# d150_in14.net
KiCad netlist of a schematic drawn in EAGLE
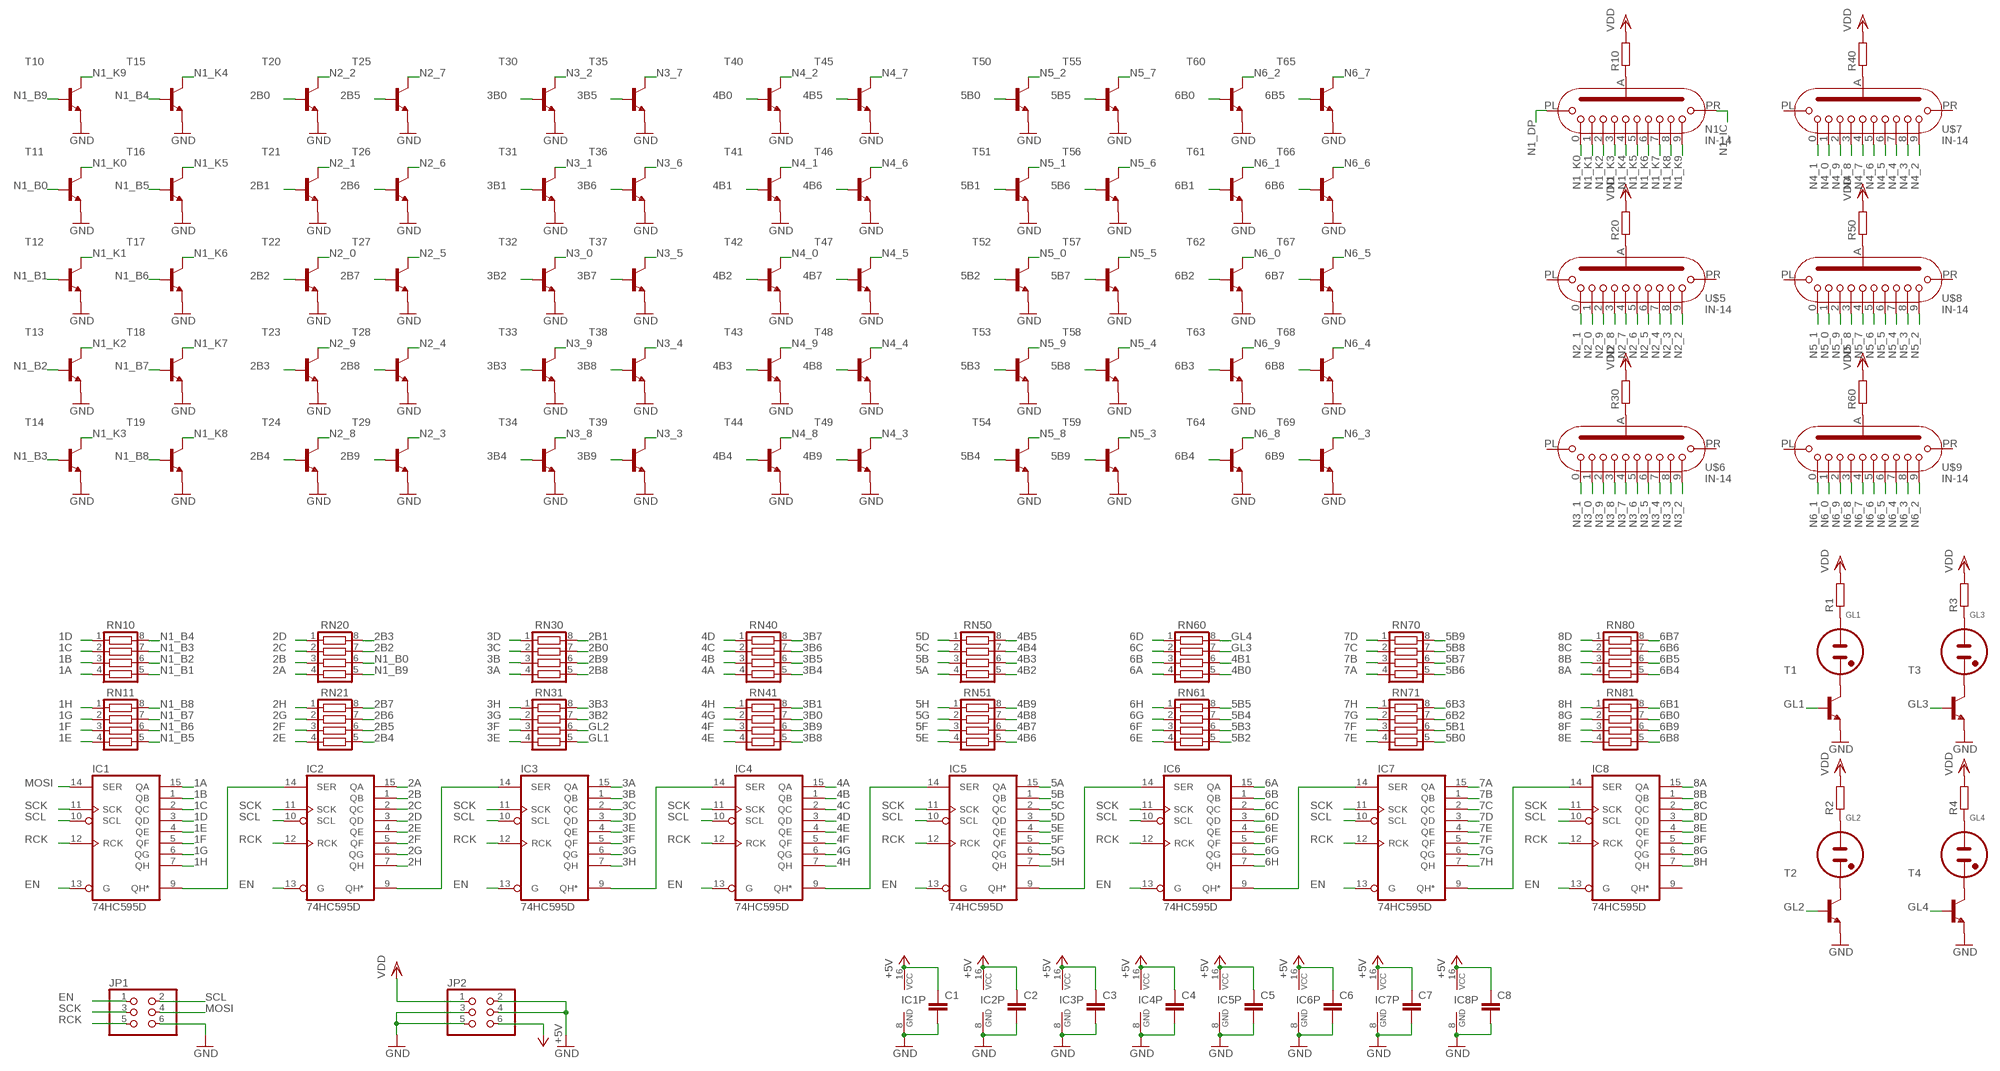
[diagram p0: schematic, sheet 1]

(export (version "E")
  (design (tool "Eeschema 10.0.6"))
  (components
    (comp (ref "C1")
      (value "C-EUC0603")
      (footprint "eagle-import:C0603")
      (libsource (lib "eagle-import") (part "C-EUC0603"))
    )
    (comp (ref "C2")
      (value "C-EUC0603")
      (footprint "eagle-import:C0603")
      (libsource (lib "eagle-import") (part "C-EUC0603"))
    )
    (comp (ref "C3")
      (value "C-EUC0603")
      (footprint "eagle-import:C0603")
      (libsource (lib "eagle-import") (part "C-EUC0603"))
    )
    (comp (ref "C4")
      (value "C-EUC0603")
      (footprint "eagle-import:C0603")
      (libsource (lib "eagle-import") (part "C-EUC0603"))
    )
    (comp (ref "C5")
      (value "C-EUC0603")
      (footprint "eagle-import:C0603")
      (libsource (lib "eagle-import") (part "C-EUC0603"))
    )
    (comp (ref "C6")
      (value "C-EUC0603")
      (footprint "eagle-import:C0603")
      (libsource (lib "eagle-import") (part "C-EUC0603"))
    )
    (comp (ref "C7")
      (value "C-EUC0603")
      (footprint "eagle-import:C0603")
      (libsource (lib "eagle-import") (part "C-EUC0603"))
    )
    (comp (ref "C8")
      (value "C-EUC0603")
      (footprint "eagle-import:C0603")
      (libsource (lib "eagle-import") (part "C-EUC0603"))
    )
    (comp (ref "GL1")
      (value "NE2-NEON-BULB-DRILL")
      (footprint "eagle-import:NE2-NEON-BULB-DRILL")
      (libsource (lib "eagle-import") (part "NE2-NEON-BULB-DRILL"))
    )
    (comp (ref "GL2")
      (value "NE2-NEON-BULB-DRILL")
      (footprint "eagle-import:NE2-NEON-BULB-DRILL")
      (libsource (lib "eagle-import") (part "NE2-NEON-BULB-DRILL"))
    )
    (comp (ref "GL3")
      (value "NE2-NEON-BULB-DRILL")
      (footprint "eagle-import:NE2-NEON-BULB-DRILL")
      (libsource (lib "eagle-import") (part "NE2-NEON-BULB-DRILL"))
    )
    (comp (ref "GL4")
      (value "NE2-NEON-BULB-DRILL")
      (footprint "eagle-import:NE2-NEON-BULB-DRILL")
      (libsource (lib "eagle-import") (part "NE2-NEON-BULB-DRILL"))
    )
    (comp (ref "IC1")
      (value "74HC595D")
      (footprint "eagle-import:SO16")
      (libsource (lib "eagle-import") (part "74595DHC"))
    )
    (comp (ref "IC2")
      (value "74HC595D")
      (footprint "eagle-import:SO16")
      (libsource (lib "eagle-import") (part "74595DHC"))
    )
    (comp (ref "IC3")
      (value "74HC595D")
      (footprint "eagle-import:SO16")
      (libsource (lib "eagle-import") (part "74595DHC"))
    )
    (comp (ref "IC4")
      (value "74HC595D")
      (footprint "eagle-import:SO16")
      (libsource (lib "eagle-import") (part "74595DHC"))
    )
    (comp (ref "IC5")
      (value "74HC595D")
      (footprint "eagle-import:SO16")
      (libsource (lib "eagle-import") (part "74595DHC"))
    )
    (comp (ref "IC6")
      (value "74HC595D")
      (footprint "eagle-import:SO16")
      (libsource (lib "eagle-import") (part "74595DHC"))
    )
    (comp (ref "IC7")
      (value "74HC595D")
      (footprint "eagle-import:SO16")
      (libsource (lib "eagle-import") (part "74595DHC"))
    )
    (comp (ref "IC8")
      (value "74HC595D")
      (footprint "eagle-import:SO16")
      (libsource (lib "eagle-import") (part "74595DHC"))
    )
    (comp (ref "JP1")
      (value "PINHD-2X3_2.54-SMD")
      (footprint "eagle-import:2X03SMD")
      (libsource (lib "eagle-import") (part "PINHD-2X3_2.54-SMD"))
    )
    (comp (ref "JP2")
      (value "PINHD-2X3_2.54-SMD")
      (footprint "eagle-import:2X03SMD")
      (libsource (lib "eagle-import") (part "PINHD-2X3_2.54-SMD"))
    )
    (comp (ref "N1")
      (value "IN-14")
      (footprint "eagle-import:IN-14")
      (libsource (lib "eagle-import") (part "IN-14"))
    )
    (comp (ref "R1")
      (value "R-EU_R0603")
      (footprint "eagle-import:R0603")
      (libsource (lib "eagle-import") (part "R-EU_R0603"))
    )
    (comp (ref "R2")
      (value "R-EU_R0603")
      (footprint "eagle-import:R0603")
      (libsource (lib "eagle-import") (part "R-EU_R0603"))
    )
    (comp (ref "R3")
      (value "R-EU_R0603")
      (footprint "eagle-import:R0603")
      (libsource (lib "eagle-import") (part "R-EU_R0603"))
    )
    (comp (ref "R4")
      (value "R-EU_R0603")
      (footprint "eagle-import:R0603")
      (libsource (lib "eagle-import") (part "R-EU_R0603"))
    )
    (comp (ref "R10")
      (value "R-EU_R0603")
      (footprint "eagle-import:R0603")
      (libsource (lib "eagle-import") (part "R-EU_R0603"))
    )
    (comp (ref "R20")
      (value "R-EU_R0603")
      (footprint "eagle-import:R0603")
      (libsource (lib "eagle-import") (part "R-EU_R0603"))
    )
    (comp (ref "R30")
      (value "R-EU_R0603")
      (footprint "eagle-import:R0603")
      (libsource (lib "eagle-import") (part "R-EU_R0603"))
    )
    (comp (ref "R40")
      (value "R-EU_R0603")
      (footprint "eagle-import:R0603")
      (libsource (lib "eagle-import") (part "R-EU_R0603"))
    )
    (comp (ref "R50")
      (value "R-EU_R0603")
      (footprint "eagle-import:R0603")
      (libsource (lib "eagle-import") (part "R-EU_R0603"))
    )
    (comp (ref "R60")
      (value "R-EU_R0603")
      (footprint "eagle-import:R0603")
      (libsource (lib "eagle-import") (part "R-EU_R0603"))
    )
    (comp (ref "RN10")
      (value "CTS742C083")
      (footprint "eagle-import:CTS742C083")
      (fields (field (name "OC_FARNELL") "unknown") (field (name "OC_NEWARK") "unknown"))
      (libsource (lib "eagle-import") (part "CTS742C083"))
    )
    (comp (ref "RN11")
      (value "CTS742C083")
      (footprint "eagle-import:CTS742C083")
      (fields (field (name "OC_FARNELL") "unknown") (field (name "OC_NEWARK") "unknown"))
      (libsource (lib "eagle-import") (part "CTS742C083"))
    )
    (comp (ref "RN20")
      (value "CTS742C083")
      (footprint "eagle-import:CTS742C083")
      (fields (field (name "OC_FARNELL") "unknown") (field (name "OC_NEWARK") "unknown"))
      (libsource (lib "eagle-import") (part "CTS742C083"))
    )
    (comp (ref "RN21")
      (value "CTS742C083")
      (footprint "eagle-import:CTS742C083")
      (fields (field (name "OC_FARNELL") "unknown") (field (name "OC_NEWARK") "unknown"))
      (libsource (lib "eagle-import") (part "CTS742C083"))
    )
    (comp (ref "RN30")
      (value "CTS742C083")
      (footprint "eagle-import:CTS742C083")
      (fields (field (name "OC_FARNELL") "unknown") (field (name "OC_NEWARK") "unknown"))
      (libsource (lib "eagle-import") (part "CTS742C083"))
    )
    (comp (ref "RN31")
      (value "CTS742C083")
      (footprint "eagle-import:CTS742C083")
      (fields (field (name "OC_FARNELL") "unknown") (field (name "OC_NEWARK") "unknown"))
      (libsource (lib "eagle-import") (part "CTS742C083"))
    )
    (comp (ref "RN40")
      (value "CTS742C083")
      (footprint "eagle-import:CTS742C083")
      (fields (field (name "OC_FARNELL") "unknown") (field (name "OC_NEWARK") "unknown"))
      (libsource (lib "eagle-import") (part "CTS742C083"))
    )
    (comp (ref "RN41")
      (value "CTS742C083")
      (footprint "eagle-import:CTS742C083")
      (fields (field (name "OC_FARNELL") "unknown") (field (name "OC_NEWARK") "unknown"))
      (libsource (lib "eagle-import") (part "CTS742C083"))
    )
    (comp (ref "RN50")
      (value "CTS742C083")
      (footprint "eagle-import:CTS742C083")
      (fields (field (name "OC_FARNELL") "unknown") (field (name "OC_NEWARK") "unknown"))
      (libsource (lib "eagle-import") (part "CTS742C083"))
    )
    (comp (ref "RN51")
      (value "CTS742C083")
      (footprint "eagle-import:CTS742C083")
      (fields (field (name "OC_FARNELL") "unknown") (field (name "OC_NEWARK") "unknown"))
      (libsource (lib "eagle-import") (part "CTS742C083"))
    )
    (comp (ref "RN60")
      (value "CTS742C083")
      (footprint "eagle-import:CTS742C083")
      (fields (field (name "OC_FARNELL") "unknown") (field (name "OC_NEWARK") "unknown"))
      (libsource (lib "eagle-import") (part "CTS742C083"))
    )
    (comp (ref "RN61")
      (value "CTS742C083")
      (footprint "eagle-import:CTS742C083")
      (fields (field (name "OC_FARNELL") "unknown") (field (name "OC_NEWARK") "unknown"))
      (libsource (lib "eagle-import") (part "CTS742C083"))
    )
    (comp (ref "RN70")
      (value "CTS742C083")
      (footprint "eagle-import:CTS742C083")
      (fields (field (name "OC_FARNELL") "unknown") (field (name "OC_NEWARK") "unknown"))
      (libsource (lib "eagle-import") (part "CTS742C083"))
    )
    (comp (ref "RN71")
      (value "CTS742C083")
      (footprint "eagle-import:CTS742C083")
      (fields (field (name "OC_FARNELL") "unknown") (field (name "OC_NEWARK") "unknown"))
      (libsource (lib "eagle-import") (part "CTS742C083"))
    )
    (comp (ref "RN80")
      (value "CTS742C083")
      (footprint "eagle-import:CTS742C083")
      (fields (field (name "OC_FARNELL") "unknown") (field (name "OC_NEWARK") "unknown"))
      (libsource (lib "eagle-import") (part "CTS742C083"))
    )
    (comp (ref "RN81")
      (value "CTS742C083")
      (footprint "eagle-import:CTS742C083")
      (fields (field (name "OC_FARNELL") "unknown") (field (name "OC_NEWARK") "unknown"))
      (libsource (lib "eagle-import") (part "CTS742C083"))
    )
    (comp (ref "T1")
      (value "SMBTA42")
      (footprint "eagle-import:SOT23")
      (libsource (lib "eagle-import") (part "SMBTA42"))
    )
    (comp (ref "T2")
      (value "SMBTA42")
      (footprint "eagle-import:SOT23")
      (libsource (lib "eagle-import") (part "SMBTA42"))
    )
    (comp (ref "T3")
      (value "SMBTA42")
      (footprint "eagle-import:SOT23")
      (libsource (lib "eagle-import") (part "SMBTA42"))
    )
    (comp (ref "T4")
      (value "SMBTA42")
      (footprint "eagle-import:SOT23")
      (libsource (lib "eagle-import") (part "SMBTA42"))
    )
    (comp (ref "T10")
      (value "SMBTA42")
      (footprint "eagle-import:SOT23")
      (libsource (lib "eagle-import") (part "SMBTA42"))
    )
    (comp (ref "T11")
      (value "SMBTA42")
      (footprint "eagle-import:SOT23")
      (libsource (lib "eagle-import") (part "SMBTA42"))
    )
    (comp (ref "T12")
      (value "SMBTA42")
      (footprint "eagle-import:SOT23")
      (libsource (lib "eagle-import") (part "SMBTA42"))
    )
    (comp (ref "T13")
      (value "SMBTA42")
      (footprint "eagle-import:SOT23")
      (libsource (lib "eagle-import") (part "SMBTA42"))
    )
    (comp (ref "T14")
      (value "SMBTA42")
      (footprint "eagle-import:SOT23")
      (libsource (lib "eagle-import") (part "SMBTA42"))
    )
    (comp (ref "T15")
      (value "SMBTA42")
      (footprint "eagle-import:SOT23")
      (libsource (lib "eagle-import") (part "SMBTA42"))
    )
    (comp (ref "T16")
      (value "SMBTA42")
      (footprint "eagle-import:SOT23")
      (libsource (lib "eagle-import") (part "SMBTA42"))
    )
    (comp (ref "T17")
      (value "SMBTA42")
      (footprint "eagle-import:SOT23")
      (libsource (lib "eagle-import") (part "SMBTA42"))
    )
    (comp (ref "T18")
      (value "SMBTA42")
      (footprint "eagle-import:SOT23")
      (libsource (lib "eagle-import") (part "SMBTA42"))
    )
    (comp (ref "T19")
      (value "SMBTA42")
      (footprint "eagle-import:SOT23")
      (libsource (lib "eagle-import") (part "SMBTA42"))
    )
    (comp (ref "T20")
      (value "SMBTA42")
      (footprint "eagle-import:SOT23")
      (libsource (lib "eagle-import") (part "SMBTA42"))
    )
    (comp (ref "T21")
      (value "SMBTA42")
      (footprint "eagle-import:SOT23")
      (libsource (lib "eagle-import") (part "SMBTA42"))
    )
    (comp (ref "T22")
      (value "SMBTA42")
      (footprint "eagle-import:SOT23")
      (libsource (lib "eagle-import") (part "SMBTA42"))
    )
    (comp (ref "T23")
      (value "SMBTA42")
      (footprint "eagle-import:SOT23")
      (libsource (lib "eagle-import") (part "SMBTA42"))
    )
    (comp (ref "T24")
      (value "SMBTA42")
      (footprint "eagle-import:SOT23")
      (libsource (lib "eagle-import") (part "SMBTA42"))
    )
    (comp (ref "T25")
      (value "SMBTA42")
      (footprint "eagle-import:SOT23")
      (libsource (lib "eagle-import") (part "SMBTA42"))
    )
    (comp (ref "T26")
      (value "SMBTA42")
      (footprint "eagle-import:SOT23")
      (libsource (lib "eagle-import") (part "SMBTA42"))
    )
    (comp (ref "T27")
      (value "SMBTA42")
      (footprint "eagle-import:SOT23")
      (libsource (lib "eagle-import") (part "SMBTA42"))
    )
    (comp (ref "T28")
      (value "SMBTA42")
      (footprint "eagle-import:SOT23")
      (libsource (lib "eagle-import") (part "SMBTA42"))
    )
    (comp (ref "T29")
      (value "SMBTA42")
      (footprint "eagle-import:SOT23")
      (libsource (lib "eagle-import") (part "SMBTA42"))
    )
    (comp (ref "T30")
      (value "SMBTA42")
      (footprint "eagle-import:SOT23")
      (libsource (lib "eagle-import") (part "SMBTA42"))
    )
    (comp (ref "T31")
      (value "SMBTA42")
      (footprint "eagle-import:SOT23")
      (libsource (lib "eagle-import") (part "SMBTA42"))
    )
    (comp (ref "T32")
      (value "SMBTA42")
      (footprint "eagle-import:SOT23")
      (libsource (lib "eagle-import") (part "SMBTA42"))
    )
    (comp (ref "T33")
      (value "SMBTA42")
      (footprint "eagle-import:SOT23")
      (libsource (lib "eagle-import") (part "SMBTA42"))
    )
    (comp (ref "T34")
      (value "SMBTA42")
      (footprint "eagle-import:SOT23")
      (libsource (lib "eagle-import") (part "SMBTA42"))
    )
    (comp (ref "T35")
      (value "SMBTA42")
      (footprint "eagle-import:SOT23")
      (libsource (lib "eagle-import") (part "SMBTA42"))
    )
    (comp (ref "T36")
      (value "SMBTA42")
      (footprint "eagle-import:SOT23")
      (libsource (lib "eagle-import") (part "SMBTA42"))
    )
    (comp (ref "T37")
      (value "SMBTA42")
      (footprint "eagle-import:SOT23")
      (libsource (lib "eagle-import") (part "SMBTA42"))
    )
    (comp (ref "T38")
      (value "SMBTA42")
      (footprint "eagle-import:SOT23")
      (libsource (lib "eagle-import") (part "SMBTA42"))
    )
    (comp (ref "T39")
      (value "SMBTA42")
      (footprint "eagle-import:SOT23")
      (libsource (lib "eagle-import") (part "SMBTA42"))
    )
    (comp (ref "T40")
      (value "SMBTA42")
      (footprint "eagle-import:SOT23")
      (libsource (lib "eagle-import") (part "SMBTA42"))
    )
    (comp (ref "T41")
      (value "SMBTA42")
      (footprint "eagle-import:SOT23")
      (libsource (lib "eagle-import") (part "SMBTA42"))
    )
    (comp (ref "T42")
      (value "SMBTA42")
      (footprint "eagle-import:SOT23")
      (libsource (lib "eagle-import") (part "SMBTA42"))
    )
    (comp (ref "T43")
      (value "SMBTA42")
      (footprint "eagle-import:SOT23")
      (libsource (lib "eagle-import") (part "SMBTA42"))
    )
    (comp (ref "T44")
      (value "SMBTA42")
      (footprint "eagle-import:SOT23")
      (libsource (lib "eagle-import") (part "SMBTA42"))
    )
    (comp (ref "T45")
      (value "SMBTA42")
      (footprint "eagle-import:SOT23")
      (libsource (lib "eagle-import") (part "SMBTA42"))
    )
    (comp (ref "T46")
      (value "SMBTA42")
      (footprint "eagle-import:SOT23")
      (libsource (lib "eagle-import") (part "SMBTA42"))
    )
    (comp (ref "T47")
      (value "SMBTA42")
      (footprint "eagle-import:SOT23")
      (libsource (lib "eagle-import") (part "SMBTA42"))
    )
    (comp (ref "T48")
      (value "SMBTA42")
      (footprint "eagle-import:SOT23")
      (libsource (lib "eagle-import") (part "SMBTA42"))
    )
    (comp (ref "T49")
      (value "SMBTA42")
      (footprint "eagle-import:SOT23")
      (libsource (lib "eagle-import") (part "SMBTA42"))
    )
    (comp (ref "T50")
      (value "SMBTA42")
      (footprint "eagle-import:SOT23")
      (libsource (lib "eagle-import") (part "SMBTA42"))
    )
    (comp (ref "T51")
      (value "SMBTA42")
      (footprint "eagle-import:SOT23")
      (libsource (lib "eagle-import") (part "SMBTA42"))
    )
    (comp (ref "T52")
      (value "SMBTA42")
      (footprint "eagle-import:SOT23")
      (libsource (lib "eagle-import") (part "SMBTA42"))
    )
    (comp (ref "T53")
      (value "SMBTA42")
      (footprint "eagle-import:SOT23")
      (libsource (lib "eagle-import") (part "SMBTA42"))
    )
    (comp (ref "T54")
      (value "SMBTA42")
      (footprint "eagle-import:SOT23")
      (libsource (lib "eagle-import") (part "SMBTA42"))
    )
    (comp (ref "T55")
      (value "SMBTA42")
      (footprint "eagle-import:SOT23")
      (libsource (lib "eagle-import") (part "SMBTA42"))
    )
    (comp (ref "T56")
      (value "SMBTA42")
      (footprint "eagle-import:SOT23")
      (libsource (lib "eagle-import") (part "SMBTA42"))
    )
    (comp (ref "T57")
      (value "SMBTA42")
      (footprint "eagle-import:SOT23")
      (libsource (lib "eagle-import") (part "SMBTA42"))
    )
    (comp (ref "T58")
      (value "SMBTA42")
      (footprint "eagle-import:SOT23")
      (libsource (lib "eagle-import") (part "SMBTA42"))
    )
    (comp (ref "T59")
      (value "SMBTA42")
      (footprint "eagle-import:SOT23")
      (libsource (lib "eagle-import") (part "SMBTA42"))
    )
    (comp (ref "T60")
      (value "SMBTA42")
      (footprint "eagle-import:SOT23")
      (libsource (lib "eagle-import") (part "SMBTA42"))
    )
    (comp (ref "T61")
      (value "SMBTA42")
      (footprint "eagle-import:SOT23")
      (libsource (lib "eagle-import") (part "SMBTA42"))
    )
    (comp (ref "T62")
      (value "SMBTA42")
      (footprint "eagle-import:SOT23")
      (libsource (lib "eagle-import") (part "SMBTA42"))
    )
    (comp (ref "T63")
      (value "SMBTA42")
      (footprint "eagle-import:SOT23")
      (libsource (lib "eagle-import") (part "SMBTA42"))
    )
    (comp (ref "T64")
      (value "SMBTA42")
      (footprint "eagle-import:SOT23")
      (libsource (lib "eagle-import") (part "SMBTA42"))
    )
    (comp (ref "T65")
      (value "SMBTA42")
      (footprint "eagle-import:SOT23")
      (libsource (lib "eagle-import") (part "SMBTA42"))
    )
    (comp (ref "T66")
      (value "SMBTA42")
      (footprint "eagle-import:SOT23")
      (libsource (lib "eagle-import") (part "SMBTA42"))
    )
    (comp (ref "T67")
      (value "SMBTA42")
      (footprint "eagle-import:SOT23")
      (libsource (lib "eagle-import") (part "SMBTA42"))
    )
    (comp (ref "T68")
      (value "SMBTA42")
      (footprint "eagle-import:SOT23")
      (libsource (lib "eagle-import") (part "SMBTA42"))
    )
    (comp (ref "T69")
      (value "SMBTA42")
      (footprint "eagle-import:SOT23")
      (libsource (lib "eagle-import") (part "SMBTA42"))
    )
    (comp (ref "U$5")
      (value "IN-14")
      (footprint "eagle-import:IN-14")
      (libsource (lib "eagle-import") (part "IN-14"))
    )
    (comp (ref "U$6")
      (value "IN-14")
      (footprint "eagle-import:IN-14")
      (libsource (lib "eagle-import") (part "IN-14"))
    )
    (comp (ref "U$7")
      (value "IN-14")
      (footprint "eagle-import:IN-14")
      (libsource (lib "eagle-import") (part "IN-14"))
    )
    (comp (ref "U$8")
      (value "IN-14")
      (footprint "eagle-import:IN-14")
      (libsource (lib "eagle-import") (part "IN-14"))
    )
    (comp (ref "U$9")
      (value "IN-14")
      (footprint "eagle-import:IN-14")
      (libsource (lib "eagle-import") (part "IN-14"))
    )
  )
  (nets
    (net (code "1") (name "+5V") (class "Default")
      (node (ref "C1") (pin "1") (pinfunction "1_1") (pintype "passive"))
      (node (ref "C2") (pin "1") (pinfunction "1_1") (pintype "passive"))
      (node (ref "C3") (pin "1") (pinfunction "1_1") (pintype "passive"))
      (node (ref "C4") (pin "1") (pinfunction "1_1") (pintype "passive"))
      (node (ref "C5") (pin "1") (pinfunction "1_1") (pintype "passive"))
      (node (ref "C6") (pin "1") (pinfunction "1_1") (pintype "passive"))
      (node (ref "C7") (pin "1") (pinfunction "1_1") (pintype "passive"))
      (node (ref "C8") (pin "1") (pinfunction "1_1") (pintype "passive"))
      (node (ref "IC1") (pin "16") (pinfunction "VCC_16") (pintype "power_in"))
      (node (ref "IC2") (pin "16") (pinfunction "VCC_16") (pintype "power_in"))
      (node (ref "IC3") (pin "16") (pinfunction "VCC_16") (pintype "power_in"))
      (node (ref "IC4") (pin "16") (pinfunction "VCC_16") (pintype "power_in"))
      (node (ref "IC5") (pin "16") (pinfunction "VCC_16") (pintype "power_in"))
      (node (ref "IC6") (pin "16") (pinfunction "VCC_16") (pintype "power_in"))
      (node (ref "IC7") (pin "16") (pinfunction "VCC_16") (pintype "power_in"))
      (node (ref "IC8") (pin "16") (pinfunction "VCC_16") (pintype "power_in"))
      (node (ref "JP2") (pin "6") (pinfunction "6_6") (pintype "passive"))
    )
    (net (code "2") (name "/1A") (class "Default")
      (node (ref "IC1") (pin "15") (pinfunction "QA_15") (pintype "tri_state"))
      (node (ref "RN10") (pin "4") (pinfunction "4_4") (pintype "passive"))
    )
    (net (code "3") (name "/1B") (class "Default")
      (node (ref "IC1") (pin "1") (pinfunction "QB_1") (pintype "tri_state"))
      (node (ref "RN10") (pin "3") (pinfunction "3_3") (pintype "passive"))
    )
    (net (code "4") (name "/1C") (class "Default")
      (node (ref "IC1") (pin "2") (pinfunction "QC_2") (pintype "tri_state"))
      (node (ref "RN10") (pin "2") (pinfunction "2_2") (pintype "passive"))
    )
    (net (code "5") (name "/1D") (class "Default")
      (node (ref "IC1") (pin "3") (pinfunction "QD_3") (pintype "tri_state"))
      (node (ref "RN10") (pin "1") (pinfunction "1_1") (pintype "passive"))
    )
    (net (code "6") (name "/1E") (class "Default")
      (node (ref "IC1") (pin "4") (pinfunction "QE_4") (pintype "tri_state"))
      (node (ref "RN11") (pin "4") (pinfunction "4_4") (pintype "passive"))
    )
    (net (code "7") (name "/1F") (class "Default")
      (node (ref "IC1") (pin "5") (pinfunction "QF_5") (pintype "tri_state"))
      (node (ref "RN11") (pin "3") (pinfunction "3_3") (pintype "passive"))
    )
    (net (code "8") (name "/1G") (class "Default")
      (node (ref "IC1") (pin "6") (pinfunction "QG_6") (pintype "tri_state"))
      (node (ref "RN11") (pin "2") (pinfunction "2_2") (pintype "passive"))
    )
    (net (code "9") (name "/1H") (class "Default")
      (node (ref "IC1") (pin "7") (pinfunction "QH_7") (pintype "tri_state"))
      (node (ref "RN11") (pin "1") (pinfunction "1_1") (pintype "passive"))
    )
    (net (code "10") (name "/2A") (class "Default")
      (node (ref "IC2") (pin "15") (pinfunction "QA_15") (pintype "tri_state"))
      (node (ref "RN20") (pin "4") (pinfunction "4_4") (pintype "passive"))
    )
    (net (code "11") (name "/2B") (class "Default")
      (node (ref "IC2") (pin "1") (pinfunction "QB_1") (pintype "tri_state"))
      (node (ref "RN20") (pin "3") (pinfunction "3_3") (pintype "passive"))
    )
    (net (code "12") (name "/2B0") (class "Default")
      (node (ref "RN30") (pin "7") (pinfunction "7_7") (pintype "passive"))
      (node (ref "T20") (pin "1") (pinfunction "B_1") (pintype "passive"))
    )
    (net (code "13") (name "/2B1") (class "Default")
      (node (ref "RN30") (pin "8") (pinfunction "8_8") (pintype "passive"))
      (node (ref "T21") (pin "1") (pinfunction "B_1") (pintype "passive"))
    )
    (net (code "14") (name "/2B2") (class "Default")
      (node (ref "RN20") (pin "7") (pinfunction "7_7") (pintype "passive"))
      (node (ref "T22") (pin "1") (pinfunction "B_1") (pintype "passive"))
    )
    (net (code "15") (name "/2B3") (class "Default")
      (node (ref "RN20") (pin "8") (pinfunction "8_8") (pintype "passive"))
      (node (ref "T23") (pin "1") (pinfunction "B_1") (pintype "passive"))
    )
    (net (code "16") (name "/2B4") (class "Default")
      (node (ref "RN21") (pin "5") (pinfunction "5_5") (pintype "passive"))
      (node (ref "T24") (pin "1") (pinfunction "B_1") (pintype "passive"))
    )
    (net (code "17") (name "/2B5") (class "Default")
      (node (ref "RN21") (pin "6") (pinfunction "6_6") (pintype "passive"))
      (node (ref "T25") (pin "1") (pinfunction "B_1") (pintype "passive"))
    )
    (net (code "18") (name "/2B6") (class "Default")
      (node (ref "RN21") (pin "7") (pinfunction "7_7") (pintype "passive"))
      (node (ref "T26") (pin "1") (pinfunction "B_1") (pintype "passive"))
    )
    (net (code "19") (name "/2B7") (class "Default")
      (node (ref "RN21") (pin "8") (pinfunction "8_8") (pintype "passive"))
      (node (ref "T27") (pin "1") (pinfunction "B_1") (pintype "passive"))
    )
    (net (code "20") (name "/2B8") (class "Default")
      (node (ref "RN30") (pin "5") (pinfunction "5_5") (pintype "passive"))
      (node (ref "T28") (pin "1") (pinfunction "B_1") (pintype "passive"))
    )
    (net (code "21") (name "/2B9") (class "Default")
      (node (ref "RN30") (pin "6") (pinfunction "6_6") (pintype "passive"))
      (node (ref "T29") (pin "1") (pinfunction "B_1") (pintype "passive"))
    )
    (net (code "22") (name "/2C") (class "Default")
      (node (ref "IC2") (pin "2") (pinfunction "QC_2") (pintype "tri_state"))
      (node (ref "RN20") (pin "2") (pinfunction "2_2") (pintype "passive"))
    )
    (net (code "23") (name "/2D") (class "Default")
      (node (ref "IC2") (pin "3") (pinfunction "QD_3") (pintype "tri_state"))
      (node (ref "RN20") (pin "1") (pinfunction "1_1") (pintype "passive"))
    )
    (net (code "24") (name "/2E") (class "Default")
      (node (ref "IC2") (pin "4") (pinfunction "QE_4") (pintype "tri_state"))
      (node (ref "RN21") (pin "4") (pinfunction "4_4") (pintype "passive"))
    )
    (net (code "25") (name "/2F") (class "Default")
      (node (ref "IC2") (pin "5") (pinfunction "QF_5") (pintype "tri_state"))
      (node (ref "RN21") (pin "3") (pinfunction "3_3") (pintype "passive"))
    )
    (net (code "26") (name "/2G") (class "Default")
      (node (ref "IC2") (pin "6") (pinfunction "QG_6") (pintype "tri_state"))
      (node (ref "RN21") (pin "2") (pinfunction "2_2") (pintype "passive"))
    )
    (net (code "27") (name "/2H") (class "Default")
      (node (ref "IC2") (pin "7") (pinfunction "QH_7") (pintype "tri_state"))
      (node (ref "RN21") (pin "1") (pinfunction "1_1") (pintype "passive"))
    )
    (net (code "28") (name "/3A") (class "Default")
      (node (ref "IC3") (pin "15") (pinfunction "QA_15") (pintype "tri_state"))
      (node (ref "RN30") (pin "4") (pinfunction "4_4") (pintype "passive"))
    )
    (net (code "29") (name "/3B") (class "Default")
      (node (ref "IC3") (pin "1") (pinfunction "QB_1") (pintype "tri_state"))
      (node (ref "RN30") (pin "3") (pinfunction "3_3") (pintype "passive"))
    )
    (net (code "30") (name "/3B0") (class "Default")
      (node (ref "RN41") (pin "7") (pinfunction "7_7") (pintype "passive"))
      (node (ref "T30") (pin "1") (pinfunction "B_1") (pintype "passive"))
    )
    (net (code "31") (name "/3B1") (class "Default")
      (node (ref "RN41") (pin "8") (pinfunction "8_8") (pintype "passive"))
      (node (ref "T31") (pin "1") (pinfunction "B_1") (pintype "passive"))
    )
    (net (code "32") (name "/3B2") (class "Default")
      (node (ref "RN31") (pin "7") (pinfunction "7_7") (pintype "passive"))
      (node (ref "T32") (pin "1") (pinfunction "B_1") (pintype "passive"))
    )
    (net (code "33") (name "/3B3") (class "Default")
      (node (ref "RN31") (pin "8") (pinfunction "8_8") (pintype "passive"))
      (node (ref "T33") (pin "1") (pinfunction "B_1") (pintype "passive"))
    )
    (net (code "34") (name "/3B4") (class "Default")
      (node (ref "RN40") (pin "5") (pinfunction "5_5") (pintype "passive"))
      (node (ref "T34") (pin "1") (pinfunction "B_1") (pintype "passive"))
    )
    (net (code "35") (name "/3B5") (class "Default")
      (node (ref "RN40") (pin "6") (pinfunction "6_6") (pintype "passive"))
      (node (ref "T35") (pin "1") (pinfunction "B_1") (pintype "passive"))
    )
    (net (code "36") (name "/3B6") (class "Default")
      (node (ref "RN40") (pin "7") (pinfunction "7_7") (pintype "passive"))
      (node (ref "T36") (pin "1") (pinfunction "B_1") (pintype "passive"))
    )
    (net (code "37") (name "/3B7") (class "Default")
      (node (ref "RN40") (pin "8") (pinfunction "8_8") (pintype "passive"))
      (node (ref "T37") (pin "1") (pinfunction "B_1") (pintype "passive"))
    )
    (net (code "38") (name "/3B8") (class "Default")
      (node (ref "RN41") (pin "5") (pinfunction "5_5") (pintype "passive"))
      (node (ref "T38") (pin "1") (pinfunction "B_1") (pintype "passive"))
    )
    (net (code "39") (name "/3B9") (class "Default")
      (node (ref "RN41") (pin "6") (pinfunction "6_6") (pintype "passive"))
      (node (ref "T39") (pin "1") (pinfunction "B_1") (pintype "passive"))
    )
    (net (code "40") (name "/3C") (class "Default")
      (node (ref "IC3") (pin "2") (pinfunction "QC_2") (pintype "tri_state"))
      (node (ref "RN30") (pin "2") (pinfunction "2_2") (pintype "passive"))
    )
    (net (code "41") (name "/3D") (class "Default")
      (node (ref "IC3") (pin "3") (pinfunction "QD_3") (pintype "tri_state"))
      (node (ref "RN30") (pin "1") (pinfunction "1_1") (pintype "passive"))
    )
    (net (code "42") (name "/3E") (class "Default")
      (node (ref "IC3") (pin "4") (pinfunction "QE_4") (pintype "tri_state"))
      (node (ref "RN31") (pin "4") (pinfunction "4_4") (pintype "passive"))
    )
    (net (code "43") (name "/3F") (class "Default")
      (node (ref "IC3") (pin "5") (pinfunction "QF_5") (pintype "tri_state"))
      (node (ref "RN31") (pin "3") (pinfunction "3_3") (pintype "passive"))
    )
    (net (code "44") (name "/3G") (class "Default")
      (node (ref "IC3") (pin "6") (pinfunction "QG_6") (pintype "tri_state"))
      (node (ref "RN31") (pin "2") (pinfunction "2_2") (pintype "passive"))
    )
    (net (code "45") (name "/3H") (class "Default")
      (node (ref "IC3") (pin "7") (pinfunction "QH_7") (pintype "tri_state"))
      (node (ref "RN31") (pin "1") (pinfunction "1_1") (pintype "passive"))
    )
    (net (code "46") (name "/4A") (class "Default")
      (node (ref "IC4") (pin "15") (pinfunction "QA_15") (pintype "tri_state"))
      (node (ref "RN40") (pin "4") (pinfunction "4_4") (pintype "passive"))
    )
    (net (code "47") (name "/4B") (class "Default")
      (node (ref "IC4") (pin "1") (pinfunction "QB_1") (pintype "tri_state"))
      (node (ref "RN40") (pin "3") (pinfunction "3_3") (pintype "passive"))
    )
    (net (code "48") (name "/4B0") (class "Default")
      (node (ref "RN60") (pin "5") (pinfunction "5_5") (pintype "passive"))
      (node (ref "T40") (pin "1") (pinfunction "B_1") (pintype "passive"))
    )
    (net (code "49") (name "/4B1") (class "Default")
      (node (ref "RN60") (pin "6") (pinfunction "6_6") (pintype "passive"))
      (node (ref "T41") (pin "1") (pinfunction "B_1") (pintype "passive"))
    )
    (net (code "50") (name "/4B2") (class "Default")
      (node (ref "RN50") (pin "5") (pinfunction "5_5") (pintype "passive"))
      (node (ref "T42") (pin "1") (pinfunction "B_1") (pintype "passive"))
    )
    (net (code "51") (name "/4B3") (class "Default")
      (node (ref "RN50") (pin "6") (pinfunction "6_6") (pintype "passive"))
      (node (ref "T43") (pin "1") (pinfunction "B_1") (pintype "passive"))
    )
    (net (code "52") (name "/4B4") (class "Default")
      (node (ref "RN50") (pin "7") (pinfunction "7_7") (pintype "passive"))
      (node (ref "T44") (pin "1") (pinfunction "B_1") (pintype "passive"))
    )
    (net (code "53") (name "/4B5") (class "Default")
      (node (ref "RN50") (pin "8") (pinfunction "8_8") (pintype "passive"))
      (node (ref "T45") (pin "1") (pinfunction "B_1") (pintype "passive"))
    )
    (net (code "54") (name "/4B6") (class "Default")
      (node (ref "RN51") (pin "5") (pinfunction "5_5") (pintype "passive"))
      (node (ref "T46") (pin "1") (pinfunction "B_1") (pintype "passive"))
    )
    (net (code "55") (name "/4B7") (class "Default")
      (node (ref "RN51") (pin "6") (pinfunction "6_6") (pintype "passive"))
      (node (ref "T47") (pin "1") (pinfunction "B_1") (pintype "passive"))
    )
    (net (code "56") (name "/4B8") (class "Default")
      (node (ref "RN51") (pin "7") (pinfunction "7_7") (pintype "passive"))
      (node (ref "T48") (pin "1") (pinfunction "B_1") (pintype "passive"))
    )
    (net (code "57") (name "/4B9") (class "Default")
      (node (ref "RN51") (pin "8") (pinfunction "8_8") (pintype "passive"))
      (node (ref "T49") (pin "1") (pinfunction "B_1") (pintype "passive"))
    )
    (net (code "58") (name "/4C") (class "Default")
      (node (ref "IC4") (pin "2") (pinfunction "QC_2") (pintype "tri_state"))
      (node (ref "RN40") (pin "2") (pinfunction "2_2") (pintype "passive"))
    )
    (net (code "59") (name "/4D") (class "Default")
      (node (ref "IC4") (pin "3") (pinfunction "QD_3") (pintype "tri_state"))
      (node (ref "RN40") (pin "1") (pinfunction "1_1") (pintype "passive"))
    )
    (net (code "60") (name "/4E") (class "Default")
      (node (ref "IC4") (pin "4") (pinfunction "QE_4") (pintype "tri_state"))
      (node (ref "RN41") (pin "4") (pinfunction "4_4") (pintype "passive"))
    )
    (net (code "61") (name "/4F") (class "Default")
      (node (ref "IC4") (pin "5") (pinfunction "QF_5") (pintype "tri_state"))
      (node (ref "RN41") (pin "3") (pinfunction "3_3") (pintype "passive"))
    )
    (net (code "62") (name "/4G") (class "Default")
      (node (ref "IC4") (pin "6") (pinfunction "QG_6") (pintype "tri_state"))
      (node (ref "RN41") (pin "2") (pinfunction "2_2") (pintype "passive"))
    )
    (net (code "63") (name "/4H") (class "Default")
      (node (ref "IC4") (pin "7") (pinfunction "QH_7") (pintype "tri_state"))
      (node (ref "RN41") (pin "1") (pinfunction "1_1") (pintype "passive"))
    )
    (net (code "64") (name "/5A") (class "Default")
      (node (ref "IC5") (pin "15") (pinfunction "QA_15") (pintype "tri_state"))
      (node (ref "RN50") (pin "4") (pinfunction "4_4") (pintype "passive"))
    )
    (net (code "65") (name "/5B") (class "Default")
      (node (ref "IC5") (pin "1") (pinfunction "QB_1") (pintype "tri_state"))
      (node (ref "RN50") (pin "3") (pinfunction "3_3") (pintype "passive"))
    )
    (net (code "66") (name "/5B0") (class "Default")
      (node (ref "RN71") (pin "5") (pinfunction "5_5") (pintype "passive"))
      (node (ref "T50") (pin "1") (pinfunction "B_1") (pintype "passive"))
    )
    (net (code "67") (name "/5B1") (class "Default")
      (node (ref "RN71") (pin "6") (pinfunction "6_6") (pintype "passive"))
      (node (ref "T51") (pin "1") (pinfunction "B_1") (pintype "passive"))
    )
    (net (code "68") (name "/5B2") (class "Default")
      (node (ref "RN61") (pin "5") (pinfunction "5_5") (pintype "passive"))
      (node (ref "T52") (pin "1") (pinfunction "B_1") (pintype "passive"))
    )
    (net (code "69") (name "/5B3") (class "Default")
      (node (ref "RN61") (pin "6") (pinfunction "6_6") (pintype "passive"))
      (node (ref "T53") (pin "1") (pinfunction "B_1") (pintype "passive"))
    )
    (net (code "70") (name "/5B4") (class "Default")
      (node (ref "RN61") (pin "7") (pinfunction "7_7") (pintype "passive"))
      (node (ref "T54") (pin "1") (pinfunction "B_1") (pintype "passive"))
    )
    (net (code "71") (name "/5B5") (class "Default")
      (node (ref "RN61") (pin "8") (pinfunction "8_8") (pintype "passive"))
      (node (ref "T55") (pin "1") (pinfunction "B_1") (pintype "passive"))
    )
    (net (code "72") (name "/5B6") (class "Default")
      (node (ref "RN70") (pin "5") (pinfunction "5_5") (pintype "passive"))
      (node (ref "T56") (pin "1") (pinfunction "B_1") (pintype "passive"))
    )
    (net (code "73") (name "/5B7") (class "Default")
      (node (ref "RN70") (pin "6") (pinfunction "6_6") (pintype "passive"))
      (node (ref "T57") (pin "1") (pinfunction "B_1") (pintype "passive"))
    )
    (net (code "74") (name "/5B8") (class "Default")
      (node (ref "RN70") (pin "7") (pinfunction "7_7") (pintype "passive"))
      (node (ref "T58") (pin "1") (pinfunction "B_1") (pintype "passive"))
    )
    (net (code "75") (name "/5B9") (class "Default")
      (node (ref "RN70") (pin "8") (pinfunction "8_8") (pintype "passive"))
      (node (ref "T59") (pin "1") (pinfunction "B_1") (pintype "passive"))
    )
    (net (code "76") (name "/5C") (class "Default")
      (node (ref "IC5") (pin "2") (pinfunction "QC_2") (pintype "tri_state"))
      (node (ref "RN50") (pin "2") (pinfunction "2_2") (pintype "passive"))
    )
    (net (code "77") (name "/5D") (class "Default")
      (node (ref "IC5") (pin "3") (pinfunction "QD_3") (pintype "tri_state"))
      (node (ref "RN50") (pin "1") (pinfunction "1_1") (pintype "passive"))
    )
    (net (code "78") (name "/5E") (class "Default")
      (node (ref "IC5") (pin "4") (pinfunction "QE_4") (pintype "tri_state"))
      (node (ref "RN51") (pin "4") (pinfunction "4_4") (pintype "passive"))
    )
    (net (code "79") (name "/5F") (class "Default")
      (node (ref "IC5") (pin "5") (pinfunction "QF_5") (pintype "tri_state"))
      (node (ref "RN51") (pin "3") (pinfunction "3_3") (pintype "passive"))
    )
    (net (code "80") (name "/5G") (class "Default")
      (node (ref "IC5") (pin "6") (pinfunction "QG_6") (pintype "tri_state"))
      (node (ref "RN51") (pin "2") (pinfunction "2_2") (pintype "passive"))
    )
    (net (code "81") (name "/5H") (class "Default")
      (node (ref "IC5") (pin "7") (pinfunction "QH_7") (pintype "tri_state"))
      (node (ref "RN51") (pin "1") (pinfunction "1_1") (pintype "passive"))
    )
    (net (code "82") (name "/6A") (class "Default")
      (node (ref "IC6") (pin "15") (pinfunction "QA_15") (pintype "tri_state"))
      (node (ref "RN60") (pin "4") (pinfunction "4_4") (pintype "passive"))
    )
    (net (code "83") (name "/6B") (class "Default")
      (node (ref "IC6") (pin "1") (pinfunction "QB_1") (pintype "tri_state"))
      (node (ref "RN60") (pin "3") (pinfunction "3_3") (pintype "passive"))
    )
    (net (code "84") (name "/6B0") (class "Default")
      (node (ref "RN81") (pin "7") (pinfunction "7_7") (pintype "passive"))
      (node (ref "T60") (pin "1") (pinfunction "B_1") (pintype "passive"))
    )
    (net (code "85") (name "/6B1") (class "Default")
      (node (ref "RN81") (pin "8") (pinfunction "8_8") (pintype "passive"))
      (node (ref "T61") (pin "1") (pinfunction "B_1") (pintype "passive"))
    )
    (net (code "86") (name "/6B2") (class "Default")
      (node (ref "RN71") (pin "7") (pinfunction "7_7") (pintype "passive"))
      (node (ref "T62") (pin "1") (pinfunction "B_1") (pintype "passive"))
    )
    (net (code "87") (name "/6B3") (class "Default")
      (node (ref "RN71") (pin "8") (pinfunction "8_8") (pintype "passive"))
      (node (ref "T63") (pin "1") (pinfunction "B_1") (pintype "passive"))
    )
    (net (code "88") (name "/6B4") (class "Default")
      (node (ref "RN80") (pin "5") (pinfunction "5_5") (pintype "passive"))
      (node (ref "T64") (pin "1") (pinfunction "B_1") (pintype "passive"))
    )
    (net (code "89") (name "/6B5") (class "Default")
      (node (ref "RN80") (pin "6") (pinfunction "6_6") (pintype "passive"))
      (node (ref "T65") (pin "1") (pinfunction "B_1") (pintype "passive"))
    )
    (net (code "90") (name "/6B6") (class "Default")
      (node (ref "RN80") (pin "7") (pinfunction "7_7") (pintype "passive"))
      (node (ref "T66") (pin "1") (pinfunction "B_1") (pintype "passive"))
    )
    (net (code "91") (name "/6B7") (class "Default")
      (node (ref "RN80") (pin "8") (pinfunction "8_8") (pintype "passive"))
      (node (ref "T67") (pin "1") (pinfunction "B_1") (pintype "passive"))
    )
    (net (code "92") (name "/6B8") (class "Default")
      (node (ref "RN81") (pin "5") (pinfunction "5_5") (pintype "passive"))
      (node (ref "T68") (pin "1") (pinfunction "B_1") (pintype "passive"))
    )
    (net (code "93") (name "/6B9") (class "Default")
      (node (ref "RN81") (pin "6") (pinfunction "6_6") (pintype "passive"))
      (node (ref "T69") (pin "1") (pinfunction "B_1") (pintype "passive"))
    )
    (net (code "94") (name "/6C") (class "Default")
      (node (ref "IC6") (pin "2") (pinfunction "QC_2") (pintype "tri_state"))
      (node (ref "RN60") (pin "2") (pinfunction "2_2") (pintype "passive"))
    )
    (net (code "95") (name "/6D") (class "Default")
      (node (ref "IC6") (pin "3") (pinfunction "QD_3") (pintype "tri_state"))
      (node (ref "RN60") (pin "1") (pinfunction "1_1") (pintype "passive"))
    )
    (net (code "96") (name "/6E") (class "Default")
      (node (ref "IC6") (pin "4") (pinfunction "QE_4") (pintype "tri_state"))
      (node (ref "RN61") (pin "4") (pinfunction "4_4") (pintype "passive"))
    )
    (net (code "97") (name "/6F") (class "Default")
      (node (ref "IC6") (pin "5") (pinfunction "QF_5") (pintype "tri_state"))
      (node (ref "RN61") (pin "3") (pinfunction "3_3") (pintype "passive"))
    )
    (net (code "98") (name "/6G") (class "Default")
      (node (ref "IC6") (pin "6") (pinfunction "QG_6") (pintype "tri_state"))
      (node (ref "RN61") (pin "2") (pinfunction "2_2") (pintype "passive"))
    )
    (net (code "99") (name "/6H") (class "Default")
      (node (ref "IC6") (pin "7") (pinfunction "QH_7") (pintype "tri_state"))
      (node (ref "RN61") (pin "1") (pinfunction "1_1") (pintype "passive"))
    )
    (net (code "100") (name "/7A") (class "Default")
      (node (ref "IC7") (pin "15") (pinfunction "QA_15") (pintype "tri_state"))
      (node (ref "RN70") (pin "4") (pinfunction "4_4") (pintype "passive"))
    )
    (net (code "101") (name "/7B") (class "Default")
      (node (ref "IC7") (pin "1") (pinfunction "QB_1") (pintype "tri_state"))
      (node (ref "RN70") (pin "3") (pinfunction "3_3") (pintype "passive"))
    )
    (net (code "102") (name "/7C") (class "Default")
      (node (ref "IC7") (pin "2") (pinfunction "QC_2") (pintype "tri_state"))
      (node (ref "RN70") (pin "2") (pinfunction "2_2") (pintype "passive"))
    )
    (net (code "103") (name "/7D") (class "Default")
      (node (ref "IC7") (pin "3") (pinfunction "QD_3") (pintype "tri_state"))
      (node (ref "RN70") (pin "1") (pinfunction "1_1") (pintype "passive"))
    )
    (net (code "104") (name "/7E") (class "Default")
      (node (ref "IC7") (pin "4") (pinfunction "QE_4") (pintype "tri_state"))
      (node (ref "RN71") (pin "4") (pinfunction "4_4") (pintype "passive"))
    )
    (net (code "105") (name "/7F") (class "Default")
      (node (ref "IC7") (pin "5") (pinfunction "QF_5") (pintype "tri_state"))
      (node (ref "RN71") (pin "3") (pinfunction "3_3") (pintype "passive"))
    )
    (net (code "106") (name "/7G") (class "Default")
      (node (ref "IC7") (pin "6") (pinfunction "QG_6") (pintype "tri_state"))
      (node (ref "RN71") (pin "2") (pinfunction "2_2") (pintype "passive"))
    )
    (net (code "107") (name "/7H") (class "Default")
      (node (ref "IC7") (pin "7") (pinfunction "QH_7") (pintype "tri_state"))
      (node (ref "RN71") (pin "1") (pinfunction "1_1") (pintype "passive"))
    )
    (net (code "108") (name "/8A") (class "Default")
      (node (ref "IC8") (pin "15") (pinfunction "QA_15") (pintype "tri_state"))
      (node (ref "RN80") (pin "4") (pinfunction "4_4") (pintype "passive"))
    )
    (net (code "109") (name "/8B") (class "Default")
      (node (ref "IC8") (pin "1") (pinfunction "QB_1") (pintype "tri_state"))
      (node (ref "RN80") (pin "3") (pinfunction "3_3") (pintype "passive"))
    )
    (net (code "110") (name "/8C") (class "Default")
      (node (ref "IC8") (pin "2") (pinfunction "QC_2") (pintype "tri_state"))
      (node (ref "RN80") (pin "2") (pinfunction "2_2") (pintype "passive"))
    )
    (net (code "111") (name "/8D") (class "Default")
      (node (ref "IC8") (pin "3") (pinfunction "QD_3") (pintype "tri_state"))
      (node (ref "RN80") (pin "1") (pinfunction "1_1") (pintype "passive"))
    )
    (net (code "112") (name "/8E") (class "Default")
      (node (ref "IC8") (pin "4") (pinfunction "QE_4") (pintype "tri_state"))
      (node (ref "RN81") (pin "4") (pinfunction "4_4") (pintype "passive"))
    )
    (net (code "113") (name "/8F") (class "Default")
      (node (ref "IC8") (pin "5") (pinfunction "QF_5") (pintype "tri_state"))
      (node (ref "RN81") (pin "3") (pinfunction "3_3") (pintype "passive"))
    )
    (net (code "114") (name "/8G") (class "Default")
      (node (ref "IC8") (pin "6") (pinfunction "QG_6") (pintype "tri_state"))
      (node (ref "RN81") (pin "2") (pinfunction "2_2") (pintype "passive"))
    )
    (net (code "115") (name "/8H") (class "Default")
      (node (ref "IC8") (pin "7") (pinfunction "QH_7") (pintype "tri_state"))
      (node (ref "RN81") (pin "1") (pinfunction "1_1") (pintype "passive"))
    )
    (net (code "116") (name "/EN") (class "Default")
      (node (ref "IC1") (pin "13") (pinfunction "G_13") (pintype "input"))
      (node (ref "IC2") (pin "13") (pinfunction "G_13") (pintype "input"))
      (node (ref "IC3") (pin "13") (pinfunction "G_13") (pintype "input"))
      (node (ref "IC4") (pin "13") (pinfunction "G_13") (pintype "input"))
      (node (ref "IC5") (pin "13") (pinfunction "G_13") (pintype "input"))
      (node (ref "IC6") (pin "13") (pinfunction "G_13") (pintype "input"))
      (node (ref "IC7") (pin "13") (pinfunction "G_13") (pintype "input"))
      (node (ref "IC8") (pin "13") (pinfunction "G_13") (pintype "input"))
      (node (ref "JP1") (pin "1") (pinfunction "1_1") (pintype "passive"))
    )
    (net (code "117") (name "/GL1") (class "Default")
      (node (ref "RN31") (pin "5") (pinfunction "5_5") (pintype "passive"))
      (node (ref "T1") (pin "1") (pinfunction "B_1") (pintype "passive"))
    )
    (net (code "118") (name "/GL2") (class "Default")
      (node (ref "RN31") (pin "6") (pinfunction "6_6") (pintype "passive"))
      (node (ref "T2") (pin "1") (pinfunction "B_1") (pintype "passive"))
    )
    (net (code "119") (name "/GL3") (class "Default")
      (node (ref "RN60") (pin "7") (pinfunction "7_7") (pintype "passive"))
      (node (ref "T3") (pin "1") (pinfunction "B_1") (pintype "passive"))
    )
    (net (code "120") (name "/GL4") (class "Default")
      (node (ref "RN60") (pin "8") (pinfunction "8_8") (pintype "passive"))
      (node (ref "T4") (pin "1") (pinfunction "B_1") (pintype "passive"))
    )
    (net (code "121") (name "/MOSI") (class "Default")
      (node (ref "IC1") (pin "14") (pinfunction "SER_14") (pintype "input"))
      (node (ref "JP1") (pin "4") (pinfunction "4_4") (pintype "passive"))
    )
    (net (code "122") (name "/N1_B0") (class "Default")
      (node (ref "RN20") (pin "6") (pinfunction "6_6") (pintype "passive"))
      (node (ref "T11") (pin "1") (pinfunction "B_1") (pintype "passive"))
    )
    (net (code "123") (name "/N1_B1") (class "Default")
      (node (ref "RN10") (pin "5") (pinfunction "5_5") (pintype "passive"))
      (node (ref "T12") (pin "1") (pinfunction "B_1") (pintype "passive"))
    )
    (net (code "124") (name "/N1_B2") (class "Default")
      (node (ref "RN10") (pin "6") (pinfunction "6_6") (pintype "passive"))
      (node (ref "T13") (pin "1") (pinfunction "B_1") (pintype "passive"))
    )
    (net (code "125") (name "/N1_B3") (class "Default")
      (node (ref "RN10") (pin "7") (pinfunction "7_7") (pintype "passive"))
      (node (ref "T14") (pin "1") (pinfunction "B_1") (pintype "passive"))
    )
    (net (code "126") (name "/N1_B4") (class "Default")
      (node (ref "RN10") (pin "8") (pinfunction "8_8") (pintype "passive"))
      (node (ref "T15") (pin "1") (pinfunction "B_1") (pintype "passive"))
    )
    (net (code "127") (name "/N1_B5") (class "Default")
      (node (ref "RN11") (pin "5") (pinfunction "5_5") (pintype "passive"))
      (node (ref "T16") (pin "1") (pinfunction "B_1") (pintype "passive"))
    )
    (net (code "128") (name "/N1_B6") (class "Default")
      (node (ref "RN11") (pin "6") (pinfunction "6_6") (pintype "passive"))
      (node (ref "T17") (pin "1") (pinfunction "B_1") (pintype "passive"))
    )
    (net (code "129") (name "/N1_B7") (class "Default")
      (node (ref "RN11") (pin "7") (pinfunction "7_7") (pintype "passive"))
      (node (ref "T18") (pin "1") (pinfunction "B_1") (pintype "passive"))
    )
    (net (code "130") (name "/N1_B8") (class "Default")
      (node (ref "RN11") (pin "8") (pinfunction "8_8") (pintype "passive"))
      (node (ref "T19") (pin "1") (pinfunction "B_1") (pintype "passive"))
    )
    (net (code "131") (name "/N1_B9") (class "Default")
      (node (ref "RN20") (pin "5") (pinfunction "5_5") (pintype "passive"))
      (node (ref "T10") (pin "1") (pinfunction "B_1") (pintype "passive"))
    )
    (net (code "132") (name "/N1_DP") (class "Default")
      (node (ref "N1") (pin "2") (pinfunction "PL_2") (pintype "bidirectional"))
    )
    (net (code "133") (name "/N1_IC") (class "Default")
      (node (ref "N1") (pin "13") (pinfunction "PR_13") (pintype "bidirectional"))
    )
    (net (code "134") (name "/N1_K0") (class "Default")
      (node (ref "N1") (pin "12") (pinfunction "0_12") (pintype "bidirectional"))
      (node (ref "T11") (pin "3") (pinfunction "C_3") (pintype "passive"))
    )
    (net (code "135") (name "/N1_K1") (class "Default")
      (node (ref "N1") (pin "3") (pinfunction "1_3") (pintype "bidirectional"))
      (node (ref "T12") (pin "3") (pinfunction "C_3") (pintype "passive"))
    )
    (net (code "136") (name "/N1_K2") (class "Default")
      (node (ref "N1") (pin "4") (pinfunction "2_4") (pintype "bidirectional"))
      (node (ref "T13") (pin "3") (pinfunction "C_3") (pintype "passive"))
    )
    (net (code "137") (name "/N1_K3") (class "Default")
      (node (ref "N1") (pin "5") (pinfunction "3_5") (pintype "bidirectional"))
      (node (ref "T14") (pin "3") (pinfunction "C_3") (pintype "passive"))
    )
    (net (code "138") (name "/N1_K4") (class "Default")
      (node (ref "N1") (pin "6") (pinfunction "4_6") (pintype "bidirectional"))
      (node (ref "T15") (pin "3") (pinfunction "C_3") (pintype "passive"))
    )
    (net (code "139") (name "/N1_K5") (class "Default")
      (node (ref "N1") (pin "7") (pinfunction "5_7") (pintype "bidirectional"))
      (node (ref "T16") (pin "3") (pinfunction "C_3") (pintype "passive"))
    )
    (net (code "140") (name "/N1_K6") (class "Default")
      (node (ref "N1") (pin "8") (pinfunction "6_8") (pintype "bidirectional"))
      (node (ref "T17") (pin "3") (pinfunction "C_3") (pintype "passive"))
    )
    (net (code "141") (name "/N1_K7") (class "Default")
      (node (ref "N1") (pin "9") (pinfunction "7_9") (pintype "bidirectional"))
      (node (ref "T18") (pin "3") (pinfunction "C_3") (pintype "passive"))
    )
    (net (code "142") (name "/N1_K8") (class "Default")
      (node (ref "N1") (pin "10") (pinfunction "8_10") (pintype "bidirectional"))
      (node (ref "T19") (pin "3") (pinfunction "C_3") (pintype "passive"))
    )
    (net (code "143") (name "/N1_K9") (class "Default")
      (node (ref "N1") (pin "11") (pinfunction "9_11") (pintype "bidirectional"))
      (node (ref "T10") (pin "3") (pinfunction "C_3") (pintype "passive"))
    )
    (net (code "144") (name "/N2_0") (class "Default")
      (node (ref "T22") (pin "3") (pinfunction "C_3") (pintype "passive"))
      (node (ref "U$5") (pin "3") (pinfunction "1_3") (pintype "bidirectional"))
    )
    (net (code "145") (name "/N2_1") (class "Default")
      (node (ref "T21") (pin "3") (pinfunction "C_3") (pintype "passive"))
      (node (ref "U$5") (pin "12") (pinfunction "0_12") (pintype "bidirectional"))
    )
    (net (code "146") (name "/N2_2") (class "Default")
      (node (ref "T20") (pin "3") (pinfunction "C_3") (pintype "passive"))
      (node (ref "U$5") (pin "11") (pinfunction "9_11") (pintype "bidirectional"))
    )
    (net (code "147") (name "/N2_3") (class "Default")
      (node (ref "T29") (pin "3") (pinfunction "C_3") (pintype "passive"))
      (node (ref "U$5") (pin "10") (pinfunction "8_10") (pintype "bidirectional"))
    )
    (net (code "148") (name "/N2_4") (class "Default")
      (node (ref "T28") (pin "3") (pinfunction "C_3") (pintype "passive"))
      (node (ref "U$5") (pin "9") (pinfunction "7_9") (pintype "bidirectional"))
    )
    (net (code "149") (name "/N2_5") (class "Default")
      (node (ref "T27") (pin "3") (pinfunction "C_3") (pintype "passive"))
      (node (ref "U$5") (pin "8") (pinfunction "6_8") (pintype "bidirectional"))
    )
    (net (code "150") (name "/N2_6") (class "Default")
      (node (ref "T26") (pin "3") (pinfunction "C_3") (pintype "passive"))
      (node (ref "U$5") (pin "7") (pinfunction "5_7") (pintype "bidirectional"))
    )
    (net (code "151") (name "/N2_7") (class "Default")
      (node (ref "T25") (pin "3") (pinfunction "C_3") (pintype "passive"))
      (node (ref "U$5") (pin "6") (pinfunction "4_6") (pintype "bidirectional"))
    )
    (net (code "152") (name "/N2_8") (class "Default")
      (node (ref "T24") (pin "3") (pinfunction "C_3") (pintype "passive"))
      (node (ref "U$5") (pin "5") (pinfunction "3_5") (pintype "bidirectional"))
    )
    (net (code "153") (name "/N2_9") (class "Default")
      (node (ref "T23") (pin "3") (pinfunction "C_3") (pintype "passive"))
      (node (ref "U$5") (pin "4") (pinfunction "2_4") (pintype "bidirectional"))
    )
    (net (code "154") (name "/N3_0") (class "Default")
      (node (ref "T32") (pin "3") (pinfunction "C_3") (pintype "passive"))
      (node (ref "U$6") (pin "3") (pinfunction "1_3") (pintype "bidirectional"))
    )
    (net (code "155") (name "/N3_1") (class "Default")
      (node (ref "T31") (pin "3") (pinfunction "C_3") (pintype "passive"))
      (node (ref "U$6") (pin "12") (pinfunction "0_12") (pintype "bidirectional"))
    )
    (net (code "156") (name "/N3_2") (class "Default")
      (node (ref "T30") (pin "3") (pinfunction "C_3") (pintype "passive"))
      (node (ref "U$6") (pin "11") (pinfunction "9_11") (pintype "bidirectional"))
    )
    (net (code "157") (name "/N3_3") (class "Default")
      (node (ref "T39") (pin "3") (pinfunction "C_3") (pintype "passive"))
      (node (ref "U$6") (pin "10") (pinfunction "8_10") (pintype "bidirectional"))
    )
    (net (code "158") (name "/N3_4") (class "Default")
      (node (ref "T38") (pin "3") (pinfunction "C_3") (pintype "passive"))
      (node (ref "U$6") (pin "9") (pinfunction "7_9") (pintype "bidirectional"))
    )
    (net (code "159") (name "/N3_5") (class "Default")
      (node (ref "T37") (pin "3") (pinfunction "C_3") (pintype "passive"))
      (node (ref "U$6") (pin "8") (pinfunction "6_8") (pintype "bidirectional"))
    )
    (net (code "160") (name "/N3_6") (class "Default")
      (node (ref "T36") (pin "3") (pinfunction "C_3") (pintype "passive"))
      (node (ref "U$6") (pin "7") (pinfunction "5_7") (pintype "bidirectional"))
    )
    (net (code "161") (name "/N3_7") (class "Default")
      (node (ref "T35") (pin "3") (pinfunction "C_3") (pintype "passive"))
      (node (ref "U$6") (pin "6") (pinfunction "4_6") (pintype "bidirectional"))
    )
    (net (code "162") (name "/N3_8") (class "Default")
      (node (ref "T34") (pin "3") (pinfunction "C_3") (pintype "passive"))
      (node (ref "U$6") (pin "5") (pinfunction "3_5") (pintype "bidirectional"))
    )
    (net (code "163") (name "/N3_9") (class "Default")
      (node (ref "T33") (pin "3") (pinfunction "C_3") (pintype "passive"))
      (node (ref "U$6") (pin "4") (pinfunction "2_4") (pintype "bidirectional"))
    )
    (net (code "164") (name "/N4_0") (class "Default")
      (node (ref "T42") (pin "3") (pinfunction "C_3") (pintype "passive"))
      (node (ref "U$7") (pin "3") (pinfunction "1_3") (pintype "bidirectional"))
    )
    (net (code "165") (name "/N4_1") (class "Default")
      (node (ref "T41") (pin "3") (pinfunction "C_3") (pintype "passive"))
      (node (ref "U$7") (pin "12") (pinfunction "0_12") (pintype "bidirectional"))
    )
    (net (code "166") (name "/N4_2") (class "Default")
      (node (ref "T40") (pin "3") (pinfunction "C_3") (pintype "passive"))
      (node (ref "U$7") (pin "11") (pinfunction "9_11") (pintype "bidirectional"))
    )
    (net (code "167") (name "/N4_3") (class "Default")
      (node (ref "T49") (pin "3") (pinfunction "C_3") (pintype "passive"))
      (node (ref "U$7") (pin "10") (pinfunction "8_10") (pintype "bidirectional"))
    )
    (net (code "168") (name "/N4_4") (class "Default")
      (node (ref "T48") (pin "3") (pinfunction "C_3") (pintype "passive"))
      (node (ref "U$7") (pin "9") (pinfunction "7_9") (pintype "bidirectional"))
    )
    (net (code "169") (name "/N4_5") (class "Default")
      (node (ref "T47") (pin "3") (pinfunction "C_3") (pintype "passive"))
      (node (ref "U$7") (pin "8") (pinfunction "6_8") (pintype "bidirectional"))
    )
    (net (code "170") (name "/N4_6") (class "Default")
      (node (ref "T46") (pin "3") (pinfunction "C_3") (pintype "passive"))
      (node (ref "U$7") (pin "7") (pinfunction "5_7") (pintype "bidirectional"))
    )
    (net (code "171") (name "/N4_7") (class "Default")
      (node (ref "T45") (pin "3") (pinfunction "C_3") (pintype "passive"))
      (node (ref "U$7") (pin "6") (pinfunction "4_6") (pintype "bidirectional"))
    )
    (net (code "172") (name "/N4_8") (class "Default")
      (node (ref "T44") (pin "3") (pinfunction "C_3") (pintype "passive"))
      (node (ref "U$7") (pin "5") (pinfunction "3_5") (pintype "bidirectional"))
    )
    (net (code "173") (name "/N4_9") (class "Default")
      (node (ref "T43") (pin "3") (pinfunction "C_3") (pintype "passive"))
      (node (ref "U$7") (pin "4") (pinfunction "2_4") (pintype "bidirectional"))
    )
    (net (code "174") (name "/N5_0") (class "Default")
      (node (ref "T52") (pin "3") (pinfunction "C_3") (pintype "passive"))
      (node (ref "U$8") (pin "3") (pinfunction "1_3") (pintype "bidirectional"))
    )
    (net (code "175") (name "/N5_1") (class "Default")
      (node (ref "T51") (pin "3") (pinfunction "C_3") (pintype "passive"))
      (node (ref "U$8") (pin "12") (pinfunction "0_12") (pintype "bidirectional"))
    )
    (net (code "176") (name "/N5_2") (class "Default")
      (node (ref "T50") (pin "3") (pinfunction "C_3") (pintype "passive"))
      (node (ref "U$8") (pin "11") (pinfunction "9_11") (pintype "bidirectional"))
    )
    (net (code "177") (name "/N5_3") (class "Default")
      (node (ref "T59") (pin "3") (pinfunction "C_3") (pintype "passive"))
      (node (ref "U$8") (pin "10") (pinfunction "8_10") (pintype "bidirectional"))
    )
    (net (code "178") (name "/N5_4") (class "Default")
      (node (ref "T58") (pin "3") (pinfunction "C_3") (pintype "passive"))
      (node (ref "U$8") (pin "9") (pinfunction "7_9") (pintype "bidirectional"))
    )
    (net (code "179") (name "/N5_5") (class "Default")
      (node (ref "T57") (pin "3") (pinfunction "C_3") (pintype "passive"))
      (node (ref "U$8") (pin "8") (pinfunction "6_8") (pintype "bidirectional"))
    )
    (net (code "180") (name "/N5_6") (class "Default")
      (node (ref "T56") (pin "3") (pinfunction "C_3") (pintype "passive"))
      (node (ref "U$8") (pin "7") (pinfunction "5_7") (pintype "bidirectional"))
    )
    (net (code "181") (name "/N5_7") (class "Default")
      (node (ref "T55") (pin "3") (pinfunction "C_3") (pintype "passive"))
      (node (ref "U$8") (pin "6") (pinfunction "4_6") (pintype "bidirectional"))
    )
    (net (code "182") (name "/N5_8") (class "Default")
      (node (ref "T54") (pin "3") (pinfunction "C_3") (pintype "passive"))
      (node (ref "U$8") (pin "5") (pinfunction "3_5") (pintype "bidirectional"))
    )
    (net (code "183") (name "/N5_9") (class "Default")
      (node (ref "T53") (pin "3") (pinfunction "C_3") (pintype "passive"))
      (node (ref "U$8") (pin "4") (pinfunction "2_4") (pintype "bidirectional"))
    )
    (net (code "184") (name "/N6_0") (class "Default")
      (node (ref "T62") (pin "3") (pinfunction "C_3") (pintype "passive"))
      (node (ref "U$9") (pin "3") (pinfunction "1_3") (pintype "bidirectional"))
    )
    (net (code "185") (name "/N6_1") (class "Default")
      (node (ref "T61") (pin "3") (pinfunction "C_3") (pintype "passive"))
      (node (ref "U$9") (pin "12") (pinfunction "0_12") (pintype "bidirectional"))
    )
    (net (code "186") (name "/N6_2") (class "Default")
      (node (ref "T60") (pin "3") (pinfunction "C_3") (pintype "passive"))
      (node (ref "U$9") (pin "11") (pinfunction "9_11") (pintype "bidirectional"))
    )
    (net (code "187") (name "/N6_3") (class "Default")
      (node (ref "T69") (pin "3") (pinfunction "C_3") (pintype "passive"))
      (node (ref "U$9") (pin "10") (pinfunction "8_10") (pintype "bidirectional"))
    )
    (net (code "188") (name "/N6_4") (class "Default")
      (node (ref "T68") (pin "3") (pinfunction "C_3") (pintype "passive"))
      (node (ref "U$9") (pin "9") (pinfunction "7_9") (pintype "bidirectional"))
    )
    (net (code "189") (name "/N6_5") (class "Default")
      (node (ref "T67") (pin "3") (pinfunction "C_3") (pintype "passive"))
      (node (ref "U$9") (pin "8") (pinfunction "6_8") (pintype "bidirectional"))
    )
    (net (code "190") (name "/N6_6") (class "Default")
      (node (ref "T66") (pin "3") (pinfunction "C_3") (pintype "passive"))
      (node (ref "U$9") (pin "7") (pinfunction "5_7") (pintype "bidirectional"))
    )
    (net (code "191") (name "/N6_7") (class "Default")
      (node (ref "T65") (pin "3") (pinfunction "C_3") (pintype "passive"))
      (node (ref "U$9") (pin "6") (pinfunction "4_6") (pintype "bidirectional"))
    )
    (net (code "192") (name "/N6_8") (class "Default")
      (node (ref "T64") (pin "3") (pinfunction "C_3") (pintype "passive"))
      (node (ref "U$9") (pin "5") (pinfunction "3_5") (pintype "bidirectional"))
    )
    (net (code "193") (name "/N6_9") (class "Default")
      (node (ref "T63") (pin "3") (pinfunction "C_3") (pintype "passive"))
      (node (ref "U$9") (pin "4") (pinfunction "2_4") (pintype "bidirectional"))
    )
    (net (code "194") (name "/RCK") (class "Default")
      (node (ref "IC1") (pin "12") (pinfunction "RCK_12") (pintype "input"))
      (node (ref "IC2") (pin "12") (pinfunction "RCK_12") (pintype "input"))
      (node (ref "IC3") (pin "12") (pinfunction "RCK_12") (pintype "input"))
      (node (ref "IC4") (pin "12") (pinfunction "RCK_12") (pintype "input"))
      (node (ref "IC5") (pin "12") (pinfunction "RCK_12") (pintype "input"))
      (node (ref "IC6") (pin "12") (pinfunction "RCK_12") (pintype "input"))
      (node (ref "IC7") (pin "12") (pinfunction "RCK_12") (pintype "input"))
      (node (ref "IC8") (pin "12") (pinfunction "RCK_12") (pintype "input"))
      (node (ref "JP1") (pin "5") (pinfunction "5_5") (pintype "passive"))
    )
    (net (code "195") (name "/SCK") (class "Default")
      (node (ref "IC1") (pin "11") (pinfunction "SCK_11") (pintype "input"))
      (node (ref "IC2") (pin "11") (pinfunction "SCK_11") (pintype "input"))
      (node (ref "IC3") (pin "11") (pinfunction "SCK_11") (pintype "input"))
      (node (ref "IC4") (pin "11") (pinfunction "SCK_11") (pintype "input"))
      (node (ref "IC5") (pin "11") (pinfunction "SCK_11") (pintype "input"))
      (node (ref "IC6") (pin "11") (pinfunction "SCK_11") (pintype "input"))
      (node (ref "IC7") (pin "11") (pinfunction "SCK_11") (pintype "input"))
      (node (ref "IC8") (pin "11") (pinfunction "SCK_11") (pintype "input"))
      (node (ref "JP1") (pin "3") (pinfunction "3_3") (pintype "passive"))
    )
    (net (code "196") (name "/SCL") (class "Default")
      (node (ref "IC1") (pin "10") (pinfunction "SCL_10") (pintype "input"))
      (node (ref "IC2") (pin "10") (pinfunction "SCL_10") (pintype "input"))
      (node (ref "IC3") (pin "10") (pinfunction "SCL_10") (pintype "input"))
      (node (ref "IC4") (pin "10") (pinfunction "SCL_10") (pintype "input"))
      (node (ref "IC5") (pin "10") (pinfunction "SCL_10") (pintype "input"))
      (node (ref "IC6") (pin "10") (pinfunction "SCL_10") (pintype "input"))
      (node (ref "IC7") (pin "10") (pinfunction "SCL_10") (pintype "input"))
      (node (ref "IC8") (pin "10") (pinfunction "SCL_10") (pintype "input"))
      (node (ref "JP1") (pin "2") (pinfunction "2_2") (pintype "passive"))
    )
    (net (code "197") (name "GND") (class "Default")
      (node (ref "C1") (pin "2") (pinfunction "2_2") (pintype "passive"))
      (node (ref "C2") (pin "2") (pinfunction "2_2") (pintype "passive"))
      (node (ref "C3") (pin "2") (pinfunction "2_2") (pintype "passive"))
      (node (ref "C4") (pin "2") (pinfunction "2_2") (pintype "passive"))
      (node (ref "C5") (pin "2") (pinfunction "2_2") (pintype "passive"))
      (node (ref "C6") (pin "2") (pinfunction "2_2") (pintype "passive"))
      (node (ref "C7") (pin "2") (pinfunction "2_2") (pintype "passive"))
      (node (ref "C8") (pin "2") (pinfunction "2_2") (pintype "passive"))
      (node (ref "IC1") (pin "8") (pinfunction "GND_8") (pintype "power_in"))
      (node (ref "IC2") (pin "8") (pinfunction "GND_8") (pintype "power_in"))
      (node (ref "IC3") (pin "8") (pinfunction "GND_8") (pintype "power_in"))
      (node (ref "IC4") (pin "8") (pinfunction "GND_8") (pintype "power_in"))
      (node (ref "IC5") (pin "8") (pinfunction "GND_8") (pintype "power_in"))
      (node (ref "IC6") (pin "8") (pinfunction "GND_8") (pintype "power_in"))
      (node (ref "IC7") (pin "8") (pinfunction "GND_8") (pintype "power_in"))
      (node (ref "IC8") (pin "8") (pinfunction "GND_8") (pintype "power_in"))
      (node (ref "JP1") (pin "6") (pinfunction "6_6") (pintype "passive"))
      (node (ref "JP2") (pin "2") (pinfunction "2_2") (pintype "passive"))
      (node (ref "JP2") (pin "3") (pinfunction "3_3") (pintype "passive"))
      (node (ref "JP2") (pin "4") (pinfunction "4_4") (pintype "passive"))
      (node (ref "JP2") (pin "5") (pinfunction "5_5") (pintype "passive"))
      (node (ref "T1") (pin "2") (pinfunction "E_2") (pintype "passive"))
      (node (ref "T10") (pin "2") (pinfunction "E_2") (pintype "passive"))
      (node (ref "T11") (pin "2") (pinfunction "E_2") (pintype "passive"))
      (node (ref "T12") (pin "2") (pinfunction "E_2") (pintype "passive"))
      (node (ref "T13") (pin "2") (pinfunction "E_2") (pintype "passive"))
      (node (ref "T14") (pin "2") (pinfunction "E_2") (pintype "passive"))
      (node (ref "T15") (pin "2") (pinfunction "E_2") (pintype "passive"))
      (node (ref "T16") (pin "2") (pinfunction "E_2") (pintype "passive"))
      (node (ref "T17") (pin "2") (pinfunction "E_2") (pintype "passive"))
      (node (ref "T18") (pin "2") (pinfunction "E_2") (pintype "passive"))
      (node (ref "T19") (pin "2") (pinfunction "E_2") (pintype "passive"))
      (node (ref "T2") (pin "2") (pinfunction "E_2") (pintype "passive"))
      (node (ref "T20") (pin "2") (pinfunction "E_2") (pintype "passive"))
      (node (ref "T21") (pin "2") (pinfunction "E_2") (pintype "passive"))
      (node (ref "T22") (pin "2") (pinfunction "E_2") (pintype "passive"))
      (node (ref "T23") (pin "2") (pinfunction "E_2") (pintype "passive"))
      (node (ref "T24") (pin "2") (pinfunction "E_2") (pintype "passive"))
      (node (ref "T25") (pin "2") (pinfunction "E_2") (pintype "passive"))
      (node (ref "T26") (pin "2") (pinfunction "E_2") (pintype "passive"))
      (node (ref "T27") (pin "2") (pinfunction "E_2") (pintype "passive"))
      (node (ref "T28") (pin "2") (pinfunction "E_2") (pintype "passive"))
      (node (ref "T29") (pin "2") (pinfunction "E_2") (pintype "passive"))
      (node (ref "T3") (pin "2") (pinfunction "E_2") (pintype "passive"))
      (node (ref "T30") (pin "2") (pinfunction "E_2") (pintype "passive"))
      (node (ref "T31") (pin "2") (pinfunction "E_2") (pintype "passive"))
      (node (ref "T32") (pin "2") (pinfunction "E_2") (pintype "passive"))
      (node (ref "T33") (pin "2") (pinfunction "E_2") (pintype "passive"))
      (node (ref "T34") (pin "2") (pinfunction "E_2") (pintype "passive"))
      (node (ref "T35") (pin "2") (pinfunction "E_2") (pintype "passive"))
      (node (ref "T36") (pin "2") (pinfunction "E_2") (pintype "passive"))
      (node (ref "T37") (pin "2") (pinfunction "E_2") (pintype "passive"))
      (node (ref "T38") (pin "2") (pinfunction "E_2") (pintype "passive"))
      (node (ref "T39") (pin "2") (pinfunction "E_2") (pintype "passive"))
      (node (ref "T4") (pin "2") (pinfunction "E_2") (pintype "passive"))
      (node (ref "T40") (pin "2") (pinfunction "E_2") (pintype "passive"))
      (node (ref "T41") (pin "2") (pinfunction "E_2") (pintype "passive"))
      (node (ref "T42") (pin "2") (pinfunction "E_2") (pintype "passive"))
      (node (ref "T43") (pin "2") (pinfunction "E_2") (pintype "passive"))
      (node (ref "T44") (pin "2") (pinfunction "E_2") (pintype "passive"))
      (node (ref "T45") (pin "2") (pinfunction "E_2") (pintype "passive"))
      (node (ref "T46") (pin "2") (pinfunction "E_2") (pintype "passive"))
      (node (ref "T47") (pin "2") (pinfunction "E_2") (pintype "passive"))
      (node (ref "T48") (pin "2") (pinfunction "E_2") (pintype "passive"))
      (node (ref "T49") (pin "2") (pinfunction "E_2") (pintype "passive"))
      (node (ref "T50") (pin "2") (pinfunction "E_2") (pintype "passive"))
      (node (ref "T51") (pin "2") (pinfunction "E_2") (pintype "passive"))
      (node (ref "T52") (pin "2") (pinfunction "E_2") (pintype "passive"))
      (node (ref "T53") (pin "2") (pinfunction "E_2") (pintype "passive"))
      (node (ref "T54") (pin "2") (pinfunction "E_2") (pintype "passive"))
      (node (ref "T55") (pin "2") (pinfunction "E_2") (pintype "passive"))
      (node (ref "T56") (pin "2") (pinfunction "E_2") (pintype "passive"))
      (node (ref "T57") (pin "2") (pinfunction "E_2") (pintype "passive"))
      (node (ref "T58") (pin "2") (pinfunction "E_2") (pintype "passive"))
      (node (ref "T59") (pin "2") (pinfunction "E_2") (pintype "passive"))
      (node (ref "T60") (pin "2") (pinfunction "E_2") (pintype "passive"))
      (node (ref "T61") (pin "2") (pinfunction "E_2") (pintype "passive"))
      (node (ref "T62") (pin "2") (pinfunction "E_2") (pintype "passive"))
      (node (ref "T63") (pin "2") (pinfunction "E_2") (pintype "passive"))
      (node (ref "T64") (pin "2") (pinfunction "E_2") (pintype "passive"))
      (node (ref "T65") (pin "2") (pinfunction "E_2") (pintype "passive"))
      (node (ref "T66") (pin "2") (pinfunction "E_2") (pintype "passive"))
      (node (ref "T67") (pin "2") (pinfunction "E_2") (pintype "passive"))
      (node (ref "T68") (pin "2") (pinfunction "E_2") (pintype "passive"))
      (node (ref "T69") (pin "2") (pinfunction "E_2") (pintype "passive"))
    )
    (net (code "198") (name "Net-(GL1-A)") (class "Default")
      (node (ref "GL1") (pin "1") (pinfunction "A_1") (pintype "passive"))
      (node (ref "R1") (pin "1") (pinfunction "1_1") (pintype "passive"))
    )
    (net (code "199") (name "Net-(GL1-A1)") (class "Default")
      (node (ref "GL1") (pin "2") (pinfunction "A1_2") (pintype "passive"))
      (node (ref "T1") (pin "3") (pinfunction "C_3") (pintype "passive"))
    )
    (net (code "200") (name "Net-(GL2-A)") (class "Default")
      (node (ref "GL2") (pin "1") (pinfunction "A_1") (pintype "passive"))
      (node (ref "R2") (pin "1") (pinfunction "1_1") (pintype "passive"))
    )
    (net (code "201") (name "Net-(GL2-A1)") (class "Default")
      (node (ref "GL2") (pin "2") (pinfunction "A1_2") (pintype "passive"))
      (node (ref "T2") (pin "3") (pinfunction "C_3") (pintype "passive"))
    )
    (net (code "202") (name "Net-(GL3-A)") (class "Default")
      (node (ref "GL3") (pin "1") (pinfunction "A_1") (pintype "passive"))
      (node (ref "R3") (pin "1") (pinfunction "1_1") (pintype "passive"))
    )
    (net (code "203") (name "Net-(GL3-A1)") (class "Default")
      (node (ref "GL3") (pin "2") (pinfunction "A1_2") (pintype "passive"))
      (node (ref "T3") (pin "3") (pinfunction "C_3") (pintype "passive"))
    )
    (net (code "204") (name "Net-(GL4-A)") (class "Default")
      (node (ref "GL4") (pin "1") (pinfunction "A_1") (pintype "passive"))
      (node (ref "R4") (pin "1") (pinfunction "1_1") (pintype "passive"))
    )
    (net (code "205") (name "Net-(GL4-A1)") (class "Default")
      (node (ref "GL4") (pin "2") (pinfunction "A1_2") (pintype "passive"))
      (node (ref "T4") (pin "3") (pinfunction "C_3") (pintype "passive"))
    )
    (net (code "206") (name "Net-(IC1A-QH*)") (class "Default")
      (node (ref "IC1") (pin "9") (pinfunction "QH*_9") (pintype "tri_state"))
      (node (ref "IC2") (pin "14") (pinfunction "SER_14") (pintype "input"))
    )
    (net (code "207") (name "Net-(IC2A-QH*)") (class "Default")
      (node (ref "IC2") (pin "9") (pinfunction "QH*_9") (pintype "tri_state"))
      (node (ref "IC3") (pin "14") (pinfunction "SER_14") (pintype "input"))
    )
    (net (code "208") (name "Net-(IC3A-QH*)") (class "Default")
      (node (ref "IC3") (pin "9") (pinfunction "QH*_9") (pintype "tri_state"))
      (node (ref "IC4") (pin "14") (pinfunction "SER_14") (pintype "input"))
    )
    (net (code "209") (name "Net-(IC4A-QH*)") (class "Default")
      (node (ref "IC4") (pin "9") (pinfunction "QH*_9") (pintype "tri_state"))
      (node (ref "IC5") (pin "14") (pinfunction "SER_14") (pintype "input"))
    )
    (net (code "210") (name "Net-(IC5A-QH*)") (class "Default")
      (node (ref "IC5") (pin "9") (pinfunction "QH*_9") (pintype "tri_state"))
      (node (ref "IC6") (pin "14") (pinfunction "SER_14") (pintype "input"))
    )
    (net (code "211") (name "Net-(IC6A-QH*)") (class "Default")
      (node (ref "IC6") (pin "9") (pinfunction "QH*_9") (pintype "tri_state"))
      (node (ref "IC7") (pin "14") (pinfunction "SER_14") (pintype "input"))
    )
    (net (code "212") (name "Net-(IC7A-QH*)") (class "Default")
      (node (ref "IC7") (pin "9") (pinfunction "QH*_9") (pintype "tri_state"))
      (node (ref "IC8") (pin "14") (pinfunction "SER_14") (pintype "input"))
    )
    (net (code "213") (name "Net-(N1-A)") (class "Default")
      (node (ref "N1") (pin "1") (pinfunction "A_1") (pintype "bidirectional"))
      (node (ref "R10") (pin "1") (pinfunction "1_1") (pintype "passive"))
    )
    (net (code "214") (name "Net-(U$5-A)") (class "Default")
      (node (ref "R20") (pin "1") (pinfunction "1_1") (pintype "passive"))
      (node (ref "U$5") (pin "1") (pinfunction "A_1") (pintype "bidirectional"))
    )
    (net (code "215") (name "Net-(U$6-A)") (class "Default")
      (node (ref "R30") (pin "1") (pinfunction "1_1") (pintype "passive"))
      (node (ref "U$6") (pin "1") (pinfunction "A_1") (pintype "bidirectional"))
    )
    (net (code "216") (name "Net-(U$7-A)") (class "Default")
      (node (ref "R40") (pin "1") (pinfunction "1_1") (pintype "passive"))
      (node (ref "U$7") (pin "1") (pinfunction "A_1") (pintype "bidirectional"))
    )
    (net (code "217") (name "Net-(U$8-A)") (class "Default")
      (node (ref "R50") (pin "1") (pinfunction "1_1") (pintype "passive"))
      (node (ref "U$8") (pin "1") (pinfunction "A_1") (pintype "bidirectional"))
    )
    (net (code "218") (name "Net-(U$9-A)") (class "Default")
      (node (ref "R60") (pin "1") (pinfunction "1_1") (pintype "passive"))
      (node (ref "U$9") (pin "1") (pinfunction "A_1") (pintype "bidirectional"))
    )
    (net (code "219") (name "VDD") (class "Default")
      (node (ref "JP2") (pin "1") (pinfunction "1_1") (pintype "passive"))
      (node (ref "R1") (pin "2") (pinfunction "2_2") (pintype "passive"))
      (node (ref "R10") (pin "2") (pinfunction "2_2") (pintype "passive"))
      (node (ref "R2") (pin "2") (pinfunction "2_2") (pintype "passive"))
      (node (ref "R20") (pin "2") (pinfunction "2_2") (pintype "passive"))
      (node (ref "R3") (pin "2") (pinfunction "2_2") (pintype "passive"))
      (node (ref "R30") (pin "2") (pinfunction "2_2") (pintype "passive"))
      (node (ref "R4") (pin "2") (pinfunction "2_2") (pintype "passive"))
      (node (ref "R40") (pin "2") (pinfunction "2_2") (pintype "passive"))
      (node (ref "R50") (pin "2") (pinfunction "2_2") (pintype "passive"))
      (node (ref "R60") (pin "2") (pinfunction "2_2") (pintype "passive"))
    )
    (net (code "220") (name "unconnected-(IC8A-QH*-Pad9)") (class "Default")
      (node (ref "IC8") (pin "9") (pinfunction "QH*_9") (pintype "tri_state"))
    )
    (net (code "221") (name "unconnected-(U$5-PL-Pad2)") (class "Default")
      (node (ref "U$5") (pin "2") (pinfunction "PL_2") (pintype "bidirectional"))
    )
    (net (code "222") (name "unconnected-(U$5-PR-Pad13)") (class "Default")
      (node (ref "U$5") (pin "13") (pinfunction "PR_13") (pintype "bidirectional"))
    )
    (net (code "223") (name "unconnected-(U$6-PL-Pad2)") (class "Default")
      (node (ref "U$6") (pin "2") (pinfunction "PL_2") (pintype "bidirectional"))
    )
    (net (code "224") (name "unconnected-(U$6-PR-Pad13)") (class "Default")
      (node (ref "U$6") (pin "13") (pinfunction "PR_13") (pintype "bidirectional"))
    )
    (net (code "225") (name "unconnected-(U$7-PL-Pad2)") (class "Default")
      (node (ref "U$7") (pin "2") (pinfunction "PL_2") (pintype "bidirectional"))
    )
    (net (code "226") (name "unconnected-(U$7-PR-Pad13)") (class "Default")
      (node (ref "U$7") (pin "13") (pinfunction "PR_13") (pintype "bidirectional"))
    )
    (net (code "227") (name "unconnected-(U$8-PL-Pad2)") (class "Default")
      (node (ref "U$8") (pin "2") (pinfunction "PL_2") (pintype "bidirectional"))
    )
    (net (code "228") (name "unconnected-(U$8-PR-Pad13)") (class "Default")
      (node (ref "U$8") (pin "13") (pinfunction "PR_13") (pintype "bidirectional"))
    )
    (net (code "229") (name "unconnected-(U$9-PL-Pad2)") (class "Default")
      (node (ref "U$9") (pin "2") (pinfunction "PL_2") (pintype "bidirectional"))
    )
    (net (code "230") (name "unconnected-(U$9-PR-Pad13)") (class "Default")
      (node (ref "U$9") (pin "13") (pinfunction "PR_13") (pintype "bidirectional"))
    )
  )
)
